# RavenLRS-Breakout.net
KiCad netlist of a schematic drawn in EAGLE
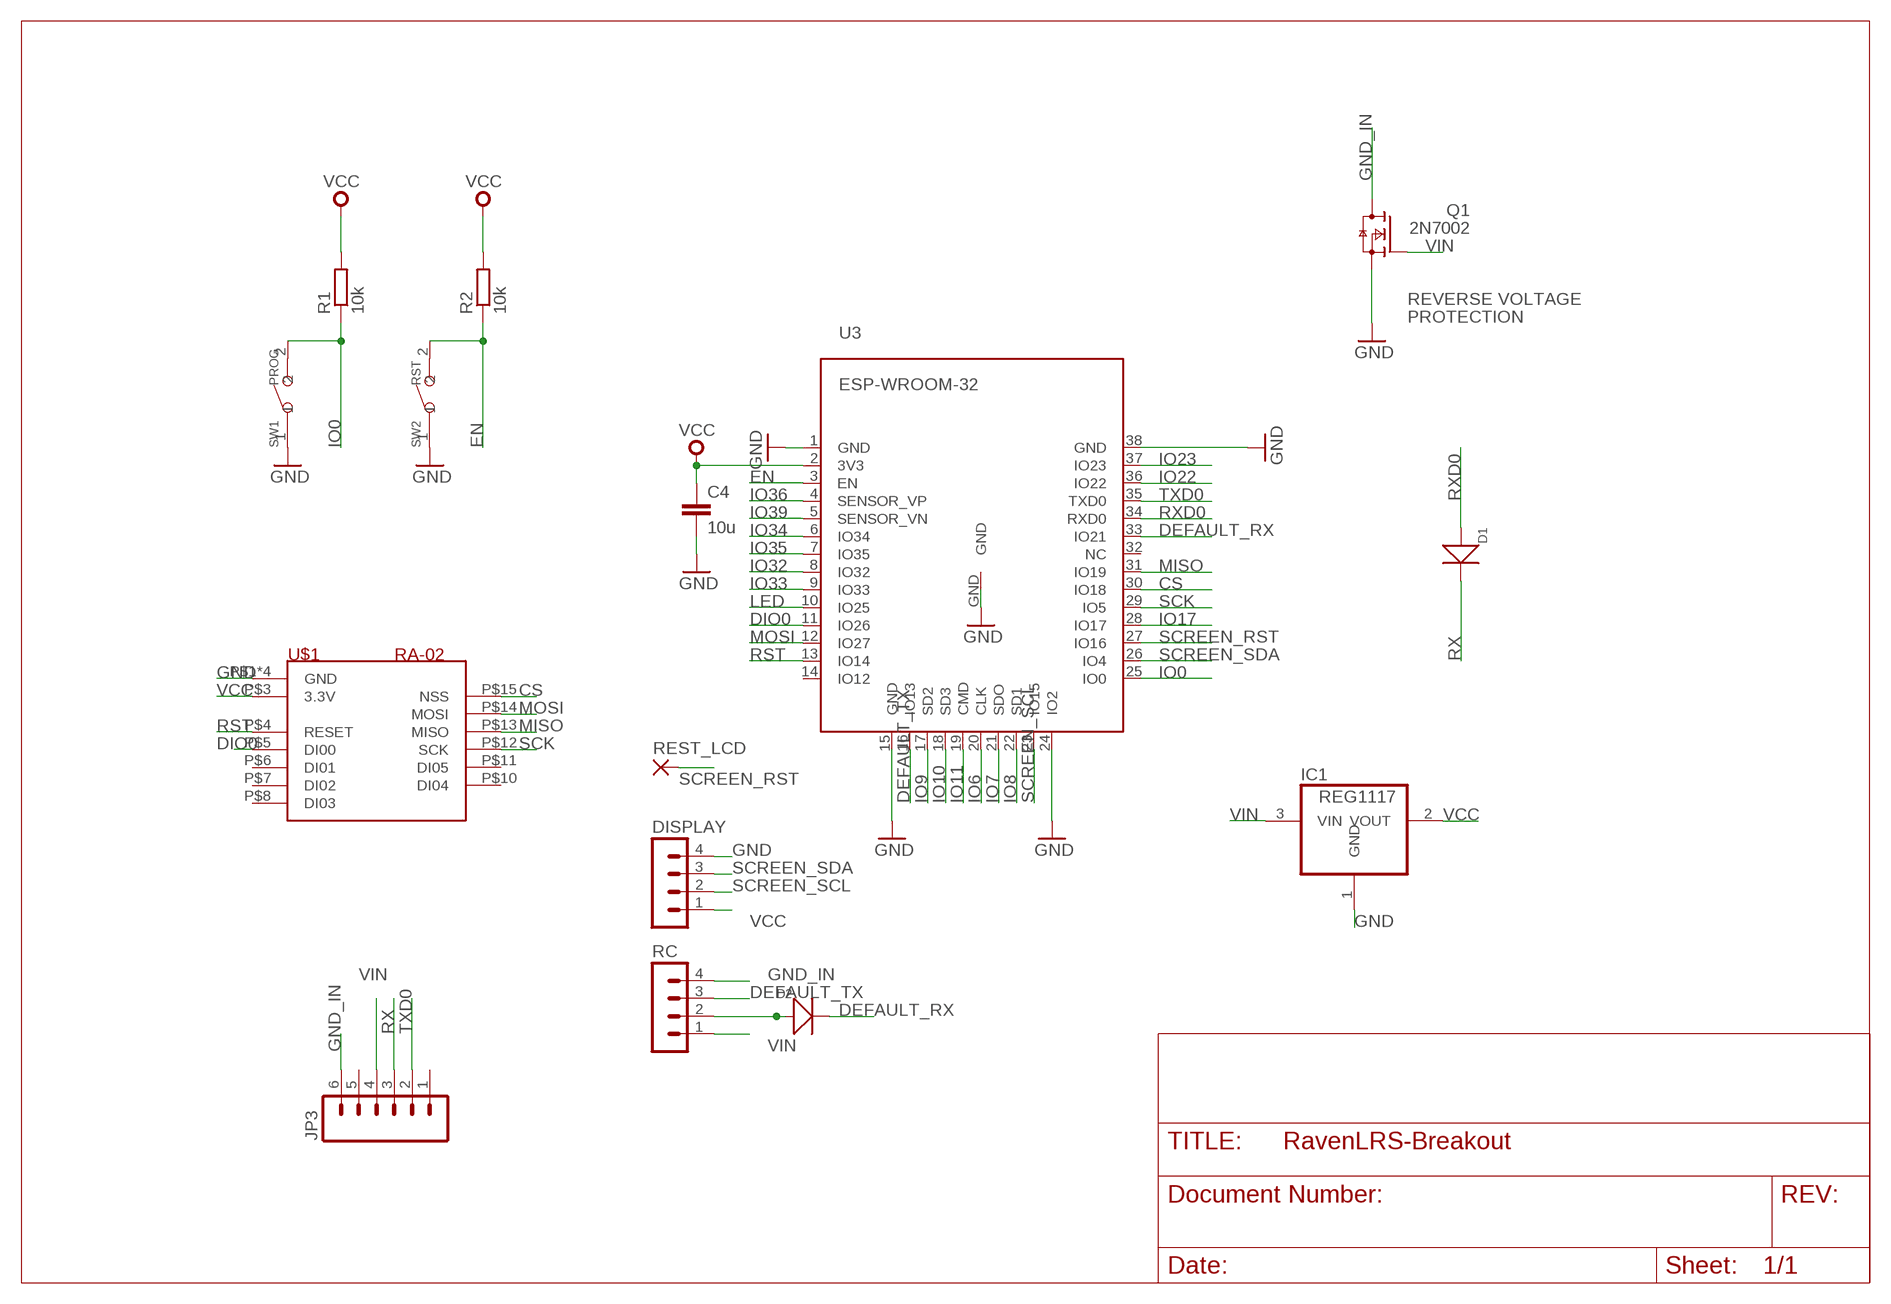
[diagram p0: schematic, sheet 1]

(export (version "E")
  (design (tool "Eeschema 10.0.6"))
  (components
    (comp (ref "C4")
      (value "10u")
      (footprint "eagle-import:C0603")
      (libsource (lib "eagle-import") (part "C-EUC0603"))
    )
    (comp (ref "D1")
      (value "DIODE'0805'")
      (footprint "eagle-import:SOD-323")
      (libsource (lib "eagle-import") (part "DIODE'0805'"))
    )
    (comp (ref "D2")
      (value "DIODE'0805'")
      (footprint "eagle-import:SOD-323")
      (libsource (lib "eagle-import") (part "DIODE'0805'"))
    )
    (comp (ref "DISPLAY")
      (value "MA04-1")
      (footprint "eagle-import:MA04-1")
      (libsource (lib "eagle-import") (part "MA04-1"))
    )
    (comp (ref "IC1")
      (value "REG1117")
      (footprint "eagle-import:SOT223")
      (libsource (lib "eagle-import") (part "REG1117"))
    )
    (comp (ref "JP3")
      (value "M06SILK_FEMALE_PTH")
      (footprint "eagle-import:1X06")
      (libsource (lib "eagle-import") (part "M06SILK_FEMALE_PTH"))
    )
    (comp (ref "Q1")
      (value "2N7002")
      (footprint "eagle-import:SOT23")
      (libsource (lib "eagle-import") (part "2N7002E"))
    )
    (comp (ref "R1")
      (value "10k")
      (footprint "eagle-import:R0603")
      (libsource (lib "eagle-import") (part "R-EU_R0603"))
    )
    (comp (ref "R2")
      (value "10k")
      (footprint "eagle-import:R0603")
      (libsource (lib "eagle-import") (part "R-EU_R0603"))
    )
    (comp (ref "RC")
      (value "MA04-1")
      (footprint "eagle-import:MA04-1")
      (libsource (lib "eagle-import") (part "MA04-1"))
    )
    (comp (ref "REST_LCD")
      (value "SMD2")
      (footprint "eagle-import:SMD1,27-2,54")
      (libsource (lib "eagle-import") (part "SMD2"))
    )
    (comp (ref "SW1")
      (value "PROG")
      (footprint "eagle-import:SW2-4.0-6.0X3.0X2.5MM")
      (libsource (lib "eagle-import") (part "SMD-BUTTON(2P-6.0X3.0X2.5MM)-DHT-1163S"))
    )
    (comp (ref "SW2")
      (value "RST")
      (footprint "eagle-import:SW2-4.0-6.0X3.0X2.5MM")
      (libsource (lib "eagle-import") (part "SMD-BUTTON(2P-6.0X3.0X2.5MM)-DHT-1163S"))
    )
    (comp (ref "U$1")
      (value "RA-02")
      (footprint "eagle-import:RA-02")
      (libsource (lib "eagle-import") (part "RA-02"))
    )
    (comp (ref "U3")
      (value "ESP-WROOM-32")
      (footprint "eagle-import:ESP-WROOM-32")
      (libsource (lib "eagle-import") (part "ESP-WROOM-32"))
    )
  )
  (nets
    (net (code "1") (name "/CS") (class "Default")
      (node (ref "U$1") (pin "P$15") (pinfunction "NSS_P$15") (pintype "bidirectional"))
      (node (ref "U3") (pin "30") (pinfunction "IO18_30") (pintype "bidirectional"))
    )
    (net (code "2") (name "/DEFAULT_RX") (class "Default")
      (node (ref "D2") (pin "-") (pinfunction "-_-") (pintype "passive"))
      (node (ref "U3") (pin "33") (pinfunction "IO21_33") (pintype "bidirectional"))
    )
    (net (code "3") (name "/DEFAULT_TX") (class "Default")
      (node (ref "RC") (pin "3") (pinfunction "3_3") (pintype "passive"))
      (node (ref "U3") (pin "16") (pinfunction "IO13_16") (pintype "bidirectional"))
    )
    (net (code "4") (name "/DIO0") (class "Default")
      (node (ref "U$1") (pin "P$5") (pinfunction "DI00_P$5") (pintype "bidirectional"))
      (node (ref "U3") (pin "11") (pinfunction "IO26_11") (pintype "bidirectional"))
    )
    (net (code "5") (name "/EN") (class "Default")
      (node (ref "R2") (pin "1") (pinfunction "1_1") (pintype "passive"))
      (node (ref "SW2") (pin "2") (pinfunction "2_2") (pintype "bidirectional"))
      (node (ref "U3") (pin "3") (pinfunction "EN_3") (pintype "bidirectional"))
    )
    (net (code "6") (name "/GND_IN") (class "Default")
      (node (ref "JP3") (pin "6") (pinfunction "6_6") (pintype "passive"))
      (node (ref "Q1") (pin "3") (pinfunction "D_3") (pintype "passive"))
      (node (ref "RC") (pin "4") (pinfunction "4_4") (pintype "passive"))
    )
    (net (code "7") (name "/IO0") (class "Default")
      (node (ref "R1") (pin "1") (pinfunction "1_1") (pintype "passive"))
      (node (ref "SW1") (pin "2") (pinfunction "2_2") (pintype "bidirectional"))
      (node (ref "U3") (pin "25") (pinfunction "IO0_25") (pintype "bidirectional"))
    )
    (net (code "8") (name "/IO6") (class "Default")
      (node (ref "U3") (pin "20") (pinfunction "CLK_20") (pintype "bidirectional"))
    )
    (net (code "9") (name "/IO7") (class "Default")
      (node (ref "U3") (pin "21") (pinfunction "SDO_21") (pintype "bidirectional"))
    )
    (net (code "10") (name "/IO8") (class "Default")
      (node (ref "U3") (pin "22") (pinfunction "SD1_22") (pintype "bidirectional"))
    )
    (net (code "11") (name "/IO9") (class "Default")
      (node (ref "U3") (pin "17") (pinfunction "SD2_17") (pintype "bidirectional"))
    )
    (net (code "12") (name "/IO10") (class "Default")
      (node (ref "U3") (pin "18") (pinfunction "SD3_18") (pintype "bidirectional"))
    )
    (net (code "13") (name "/IO11") (class "Default")
      (node (ref "U3") (pin "19") (pinfunction "CMD_19") (pintype "bidirectional"))
    )
    (net (code "14") (name "/IO17") (class "Default")
      (node (ref "U3") (pin "28") (pinfunction "IO17_28") (pintype "bidirectional"))
    )
    (net (code "15") (name "/IO22") (class "Default")
      (node (ref "U3") (pin "36") (pinfunction "IO22_36") (pintype "bidirectional"))
    )
    (net (code "16") (name "/IO23") (class "Default")
      (node (ref "U3") (pin "37") (pinfunction "IO23_37") (pintype "bidirectional"))
    )
    (net (code "17") (name "/IO32") (class "Default")
      (node (ref "U3") (pin "8") (pinfunction "IO32_8") (pintype "bidirectional"))
    )
    (net (code "18") (name "/IO33") (class "Default")
      (node (ref "U3") (pin "9") (pinfunction "IO33_9") (pintype "bidirectional"))
    )
    (net (code "19") (name "/IO34") (class "Default")
      (node (ref "U3") (pin "6") (pinfunction "IO34_6") (pintype "bidirectional"))
    )
    (net (code "20") (name "/IO35") (class "Default")
      (node (ref "U3") (pin "7") (pinfunction "IO35_7") (pintype "bidirectional"))
    )
    (net (code "21") (name "/IO36") (class "Default")
      (node (ref "U3") (pin "4") (pinfunction "SENSOR_VP_4") (pintype "bidirectional"))
    )
    (net (code "22") (name "/IO39") (class "Default")
      (node (ref "U3") (pin "5") (pinfunction "SENSOR_VN_5") (pintype "bidirectional"))
    )
    (net (code "23") (name "/LED") (class "Default")
      (node (ref "U3") (pin "10") (pinfunction "IO25_10") (pintype "bidirectional"))
    )
    (net (code "24") (name "/MISO") (class "Default")
      (node (ref "U$1") (pin "P$13") (pinfunction "MISO_P$13") (pintype "bidirectional"))
      (node (ref "U3") (pin "31") (pinfunction "IO19_31") (pintype "bidirectional"))
    )
    (net (code "25") (name "/MOSI") (class "Default")
      (node (ref "U$1") (pin "P$14") (pinfunction "MOSI_P$14") (pintype "bidirectional"))
      (node (ref "U3") (pin "12") (pinfunction "IO27_12") (pintype "bidirectional"))
    )
    (net (code "26") (name "/RST") (class "Default")
      (node (ref "U$1") (pin "P$4") (pinfunction "RESET_P$4") (pintype "bidirectional"))
      (node (ref "U3") (pin "13") (pinfunction "IO14_13") (pintype "bidirectional"))
    )
    (net (code "27") (name "/RX") (class "Default")
      (node (ref "D1") (pin "-") (pinfunction "-_-") (pintype "passive"))
      (node (ref "JP3") (pin "3") (pinfunction "3_3") (pintype "passive"))
    )
    (net (code "28") (name "/RXD0") (class "Default")
      (node (ref "D1") (pin "+") (pinfunction "+_+") (pintype "passive"))
      (node (ref "U3") (pin "34") (pinfunction "RXD0_34") (pintype "bidirectional"))
    )
    (net (code "29") (name "/SCK") (class "Default")
      (node (ref "U$1") (pin "P$12") (pinfunction "SCK_P$12") (pintype "bidirectional"))
      (node (ref "U3") (pin "29") (pinfunction "IO5_29") (pintype "bidirectional"))
    )
    (net (code "30") (name "/SCREEN_RST") (class "Default")
      (node (ref "REST_LCD") (pin "1") (pinfunction "P_1") (pintype "passive"))
      (node (ref "U3") (pin "27") (pinfunction "IO16_27") (pintype "bidirectional"))
    )
    (net (code "31") (name "/SCREEN_SCL") (class "Default")
      (node (ref "DISPLAY") (pin "2") (pinfunction "2_2") (pintype "passive"))
      (node (ref "U3") (pin "23") (pinfunction "IO15_23") (pintype "bidirectional"))
    )
    (net (code "32") (name "/SCREEN_SDA") (class "Default")
      (node (ref "DISPLAY") (pin "3") (pinfunction "3_3") (pintype "passive"))
      (node (ref "U3") (pin "26") (pinfunction "IO4_26") (pintype "bidirectional"))
    )
    (net (code "33") (name "/TXD0") (class "Default")
      (node (ref "JP3") (pin "2") (pinfunction "2_2") (pintype "passive"))
      (node (ref "U3") (pin "35") (pinfunction "TXD0_35") (pintype "bidirectional"))
    )
    (net (code "34") (name "/VIN") (class "Default")
      (node (ref "IC1") (pin "3") (pinfunction "VIN_3") (pintype "input"))
      (node (ref "JP3") (pin "4") (pinfunction "4_4") (pintype "passive"))
      (node (ref "Q1") (pin "1") (pinfunction "G_1") (pintype "passive"))
      (node (ref "RC") (pin "1") (pinfunction "1_1") (pintype "passive"))
    )
    (net (code "35") (name "GND") (class "Default")
      (node (ref "C4") (pin "2") (pinfunction "2_2") (pintype "passive"))
      (node (ref "DISPLAY") (pin "4") (pinfunction "4_4") (pintype "passive"))
      (node (ref "IC1") (pin "1") (pinfunction "GND_1") (pintype "power_in"))
      (node (ref "Q1") (pin "2") (pinfunction "S_2") (pintype "passive"))
      (node (ref "SW1") (pin "1") (pinfunction "1_1") (pintype "bidirectional"))
      (node (ref "SW2") (pin "1") (pinfunction "1_1") (pintype "bidirectional"))
      (node (ref "U$1") (pin "P$1") (pinfunction "GND_P$1") (pintype "bidirectional"))
      (node (ref "U$1") (pin "P$16") (pinfunction "GND_P$16") (pintype "bidirectional"))
      (node (ref "U$1") (pin "P$2") (pinfunction "GND_P$2") (pintype "bidirectional"))
      (node (ref "U$1") (pin "P$9") (pinfunction "GND_P$9") (pintype "bidirectional"))
      (node (ref "U3") (pin "1") (pinfunction "GND_1") (pintype "bidirectional"))
      (node (ref "U3") (pin "15") (pinfunction "GND_15") (pintype "bidirectional"))
      (node (ref "U3") (pin "24") (pinfunction "IO2_24") (pintype "bidirectional"))
      (node (ref "U3") (pin "38") (pinfunction "GND_38") (pintype "bidirectional"))
      (node (ref "U3") (pin "GND") (pinfunction "GND_GND") (pintype "bidirectional"))
    )
    (net (code "36") (name "Net-(D2-Pad+)") (class "Default")
      (node (ref "D2") (pin "+") (pinfunction "+_+") (pintype "passive"))
      (node (ref "RC") (pin "2") (pinfunction "2_2") (pintype "passive"))
    )
    (net (code "37") (name "VCC") (class "Default")
      (node (ref "C4") (pin "1") (pinfunction "1_1") (pintype "passive"))
      (node (ref "DISPLAY") (pin "1") (pinfunction "1_1") (pintype "passive"))
      (node (ref "IC1") (pin "2") (pinfunction "VOUT_2") (pintype "output"))
      (node (ref "R1") (pin "2") (pinfunction "2_2") (pintype "passive"))
      (node (ref "R2") (pin "2") (pinfunction "2_2") (pintype "passive"))
      (node (ref "U$1") (pin "P$3") (pinfunction "3.3V_P$3") (pintype "bidirectional"))
      (node (ref "U3") (pin "2") (pinfunction "3V3_2") (pintype "bidirectional"))
    )
    (net (code "38") (name "unconnected-(JP3-Pad1)") (class "Default")
      (node (ref "JP3") (pin "1") (pinfunction "1_1") (pintype "passive"))
    )
    (net (code "39") (name "unconnected-(JP3-Pad5)") (class "Default")
      (node (ref "JP3") (pin "5") (pinfunction "5_5") (pintype "passive"))
    )
    (net (code "40") (name "unconnected-(U$1-DI01-PadP$6)") (class "Default")
      (node (ref "U$1") (pin "P$6") (pinfunction "DI01_P$6") (pintype "bidirectional"))
    )
    (net (code "41") (name "unconnected-(U$1-DI02-PadP$7)") (class "Default")
      (node (ref "U$1") (pin "P$7") (pinfunction "DI02_P$7") (pintype "bidirectional"))
    )
    (net (code "42") (name "unconnected-(U$1-DI03-PadP$8)") (class "Default")
      (node (ref "U$1") (pin "P$8") (pinfunction "DI03_P$8") (pintype "bidirectional"))
    )
    (net (code "43") (name "unconnected-(U$1-DI04-PadP$10)") (class "Default")
      (node (ref "U$1") (pin "P$10") (pinfunction "DI04_P$10") (pintype "bidirectional"))
    )
    (net (code "44") (name "unconnected-(U$1-DI05-PadP$11)") (class "Default")
      (node (ref "U$1") (pin "P$11") (pinfunction "DI05_P$11") (pintype "bidirectional"))
    )
    (net (code "45") (name "unconnected-(U3-IO12-Pad14)") (class "Default")
      (node (ref "U3") (pin "14") (pinfunction "IO12_14") (pintype "bidirectional"))
    )
    (net (code "46") (name "unconnected-(U3-NC-Pad32)") (class "Default")
      (node (ref "U3") (pin "32") (pinfunction "NC_32") (pintype "bidirectional"))
    )
  )
)
